# Alimentation.net
KiCad netlist of a schematic drawn in EAGLE
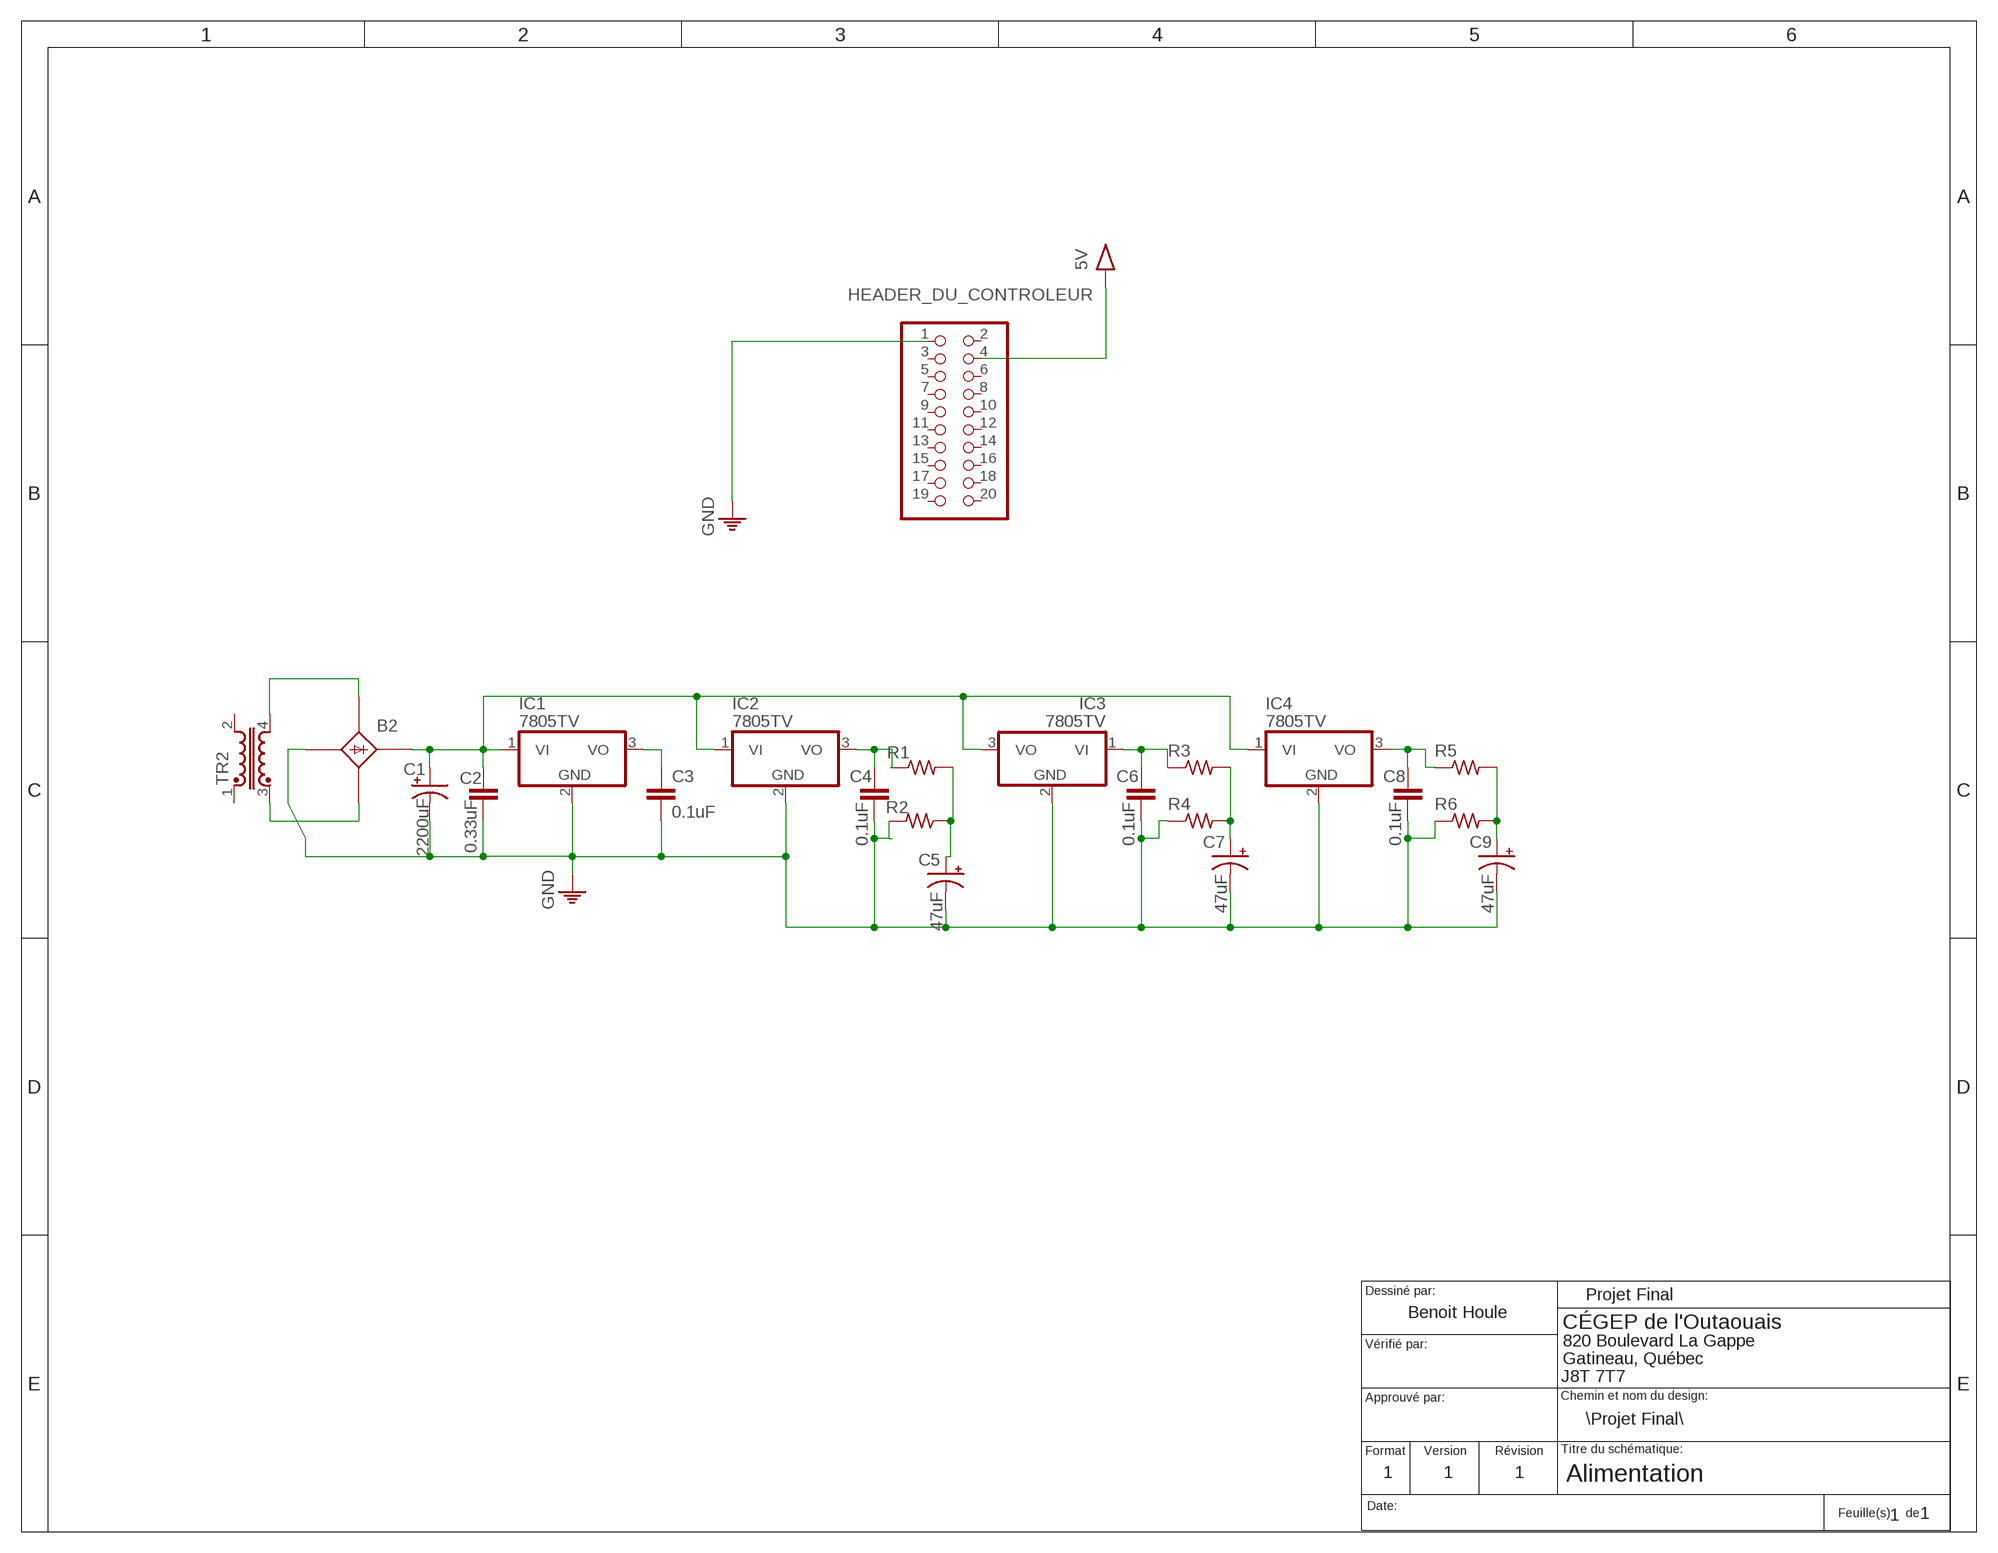
[diagram p0: schematic, sheet 1]

(export (version "E")
  (design (tool "Eeschema 10.0.6"))
  (components
    (comp (ref "B2")
      (value "B25A-")
      (footprint "eagle-import:B25A-")
      (libsource (lib "eagle-import") (part "B25A-"))
    )
    (comp (ref "C1")
      (value "2200uF")
      (footprint "eagle-import:SANYO-OSCON_B'")
      (libsource (lib "eagle-import") (part "CPOL-USSANYO_B'"))
    )
    (comp (ref "C2")
      (value "0.33uF")
      (footprint "eagle-import:C075-032X103")
      (libsource (lib "eagle-import") (part "C-EU075-032X103"))
    )
    (comp (ref "C3")
      (value "0.1uF")
      (footprint "eagle-import:C075-032X103")
      (libsource (lib "eagle-import") (part "C-EU075-032X103"))
    )
    (comp (ref "C4")
      (value "0.1uF")
      (footprint "eagle-import:C075-032X103")
      (libsource (lib "eagle-import") (part "C-EU075-032X103"))
    )
    (comp (ref "C5")
      (value "47uF")
      (footprint "eagle-import:SANYO-OSCON_B'")
      (libsource (lib "eagle-import") (part "CPOL-USSANYO_B'"))
    )
    (comp (ref "C6")
      (value "0.1uF")
      (footprint "eagle-import:C075-032X103")
      (libsource (lib "eagle-import") (part "C-EU075-032X103"))
    )
    (comp (ref "C7")
      (value "47uF")
      (footprint "eagle-import:SANYO-OSCON_B'")
      (libsource (lib "eagle-import") (part "CPOL-USSANYO_B'"))
    )
    (comp (ref "C8")
      (value "0.1uF")
      (footprint "eagle-import:C075-032X103")
      (libsource (lib "eagle-import") (part "C-EU075-032X103"))
    )
    (comp (ref "C9")
      (value "47uF")
      (footprint "eagle-import:SANYO-OSCON_B'")
      (libsource (lib "eagle-import") (part "CPOL-USSANYO_B'"))
    )
    (comp (ref "FRAME1")
      (value "CARTOUCHE_TGÉ")
      (footprint "eagle-import:CARTOUCHE")
      (libsource (lib "eagle-import") (part "CARTOUCHE_TGÉ"))
    )
    (comp (ref "HEADER_DU_CONTROLEUR")
      (value "PINHD-2X10")
      (footprint "eagle-import:2X10")
      (libsource (lib "eagle-import") (part "PINHD-2X10"))
    )
    (comp (ref "IC1")
      (value "7805TV")
      (footprint "eagle-import:TO220V")
      (libsource (lib "eagle-import") (part "78TV05"))
    )
    (comp (ref "IC2")
      (value "7805TV")
      (footprint "eagle-import:TO220V")
      (libsource (lib "eagle-import") (part "78TV05"))
    )
    (comp (ref "IC3")
      (value "7805TV")
      (footprint "eagle-import:TO220V")
      (libsource (lib "eagle-import") (part "78TV05"))
    )
    (comp (ref "IC4")
      (value "7805TV")
      (footprint "eagle-import:TO220V")
      (libsource (lib "eagle-import") (part "78TV05"))
    )
    (comp (ref "R1")
      (value "R-US_0207/15")
      (footprint "eagle-import:0207_15")
      (libsource (lib "eagle-import") (part "R-US_0207/15"))
    )
    (comp (ref "R2")
      (value "R-US_0207/15")
      (footprint "eagle-import:0207_15")
      (libsource (lib "eagle-import") (part "R-US_0207/15"))
    )
    (comp (ref "R3")
      (value "R-US_0207/15")
      (footprint "eagle-import:0207_15")
      (libsource (lib "eagle-import") (part "R-US_0207/15"))
    )
    (comp (ref "R4")
      (value "R-US_0207/15")
      (footprint "eagle-import:0207_15")
      (libsource (lib "eagle-import") (part "R-US_0207/15"))
    )
    (comp (ref "R5")
      (value "R-US_0207/15")
      (footprint "eagle-import:0207_15")
      (libsource (lib "eagle-import") (part "R-US_0207/15"))
    )
    (comp (ref "R6")
      (value "R-US_0207/15")
      (footprint "eagle-import:0207_15")
      (libsource (lib "eagle-import") (part "R-US_0207/15"))
    )
    (comp (ref "TR2")
      (value "U15-TRANSFORMER")
      (footprint "eagle-import:U15")
      (libsource (lib "eagle-import") (part "U15-TRANSFORMER"))
    )
  )
  (nets
    (net (code "1") (name "5V") (class "Default")
      (node (ref "HEADER_DU_CONTROLEUR") (pin "4") (pinfunction "4_4") (pintype "passive"))
    )
    (net (code "2") (name "GND") (class "Default")
      (node (ref "B2") (pin "-1") (pinfunction "-_-1") (pintype "passive"))
      (node (ref "C1") (pin "-") (pinfunction "-_-") (pintype "passive"))
      (node (ref "C2") (pin "2") (pinfunction "2_2") (pintype "passive"))
      (node (ref "C3") (pin "2") (pinfunction "2_2") (pintype "passive"))
      (node (ref "C4") (pin "2") (pinfunction "2_2") (pintype "passive"))
      (node (ref "C5") (pin "-") (pinfunction "-_-") (pintype "passive"))
      (node (ref "C6") (pin "2") (pinfunction "2_2") (pintype "passive"))
      (node (ref "C7") (pin "-") (pinfunction "-_-") (pintype "passive"))
      (node (ref "C8") (pin "2") (pinfunction "2_2") (pintype "passive"))
      (node (ref "C9") (pin "-") (pinfunction "-_-") (pintype "passive"))
      (node (ref "HEADER_DU_CONTROLEUR") (pin "1") (pinfunction "1_1") (pintype "passive"))
      (node (ref "IC1") (pin "2") (pinfunction "GND_2") (pintype "passive"))
      (node (ref "IC2") (pin "2") (pinfunction "GND_2") (pintype "passive"))
      (node (ref "IC3") (pin "2") (pinfunction "GND_2") (pintype "passive"))
      (node (ref "IC4") (pin "2") (pinfunction "GND_2") (pintype "passive"))
      (node (ref "R2") (pin "2") (pinfunction "2_2") (pintype "passive"))
      (node (ref "R4") (pin "1") (pinfunction "1_1") (pintype "passive"))
      (node (ref "R6") (pin "1") (pinfunction "1_1") (pintype "passive"))
    )
    (net (code "3") (name "Net-(B2-AC1-PadAC1-)") (class "Default")
      (node (ref "B2") (pin "AC1-") (pinfunction "AC1_AC1-") (pintype "passive"))
      (node (ref "TR2") (pin "4") (pinfunction "4_4") (pintype "passive"))
    )
    (net (code "4") (name "Net-(B2-AC2-PadAC2-)") (class "Default")
      (node (ref "B2") (pin "AC2-") (pinfunction "AC2_AC2-") (pintype "passive"))
      (node (ref "TR2") (pin "3") (pinfunction "3_3") (pintype "passive"))
    )
    (net (code "5") (name "Net-(C5-Pad+)") (class "Default")
      (node (ref "C5") (pin "+") (pinfunction "+_+") (pintype "passive"))
      (node (ref "R1") (pin "2") (pinfunction "2_2") (pintype "passive"))
      (node (ref "R2") (pin "1") (pinfunction "1_1") (pintype "passive"))
    )
    (net (code "6") (name "Net-(C7-Pad+)") (class "Default")
      (node (ref "C7") (pin "+") (pinfunction "+_+") (pintype "passive"))
      (node (ref "R3") (pin "2") (pinfunction "2_2") (pintype "passive"))
      (node (ref "R4") (pin "2") (pinfunction "2_2") (pintype "passive"))
    )
    (net (code "7") (name "Net-(C9-Pad+)") (class "Default")
      (node (ref "C9") (pin "+") (pinfunction "+_+") (pintype "passive"))
      (node (ref "R5") (pin "2") (pinfunction "2_2") (pintype "passive"))
      (node (ref "R6") (pin "2") (pinfunction "2_2") (pintype "passive"))
    )
    (net (code "8") (name "Net-(IC1-VI)") (class "Default")
      (node (ref "B2") (pin "+1") (pinfunction "+_+1") (pintype "passive"))
      (node (ref "C1") (pin "+") (pinfunction "+_+") (pintype "passive"))
      (node (ref "C2") (pin "1") (pinfunction "1_1") (pintype "passive"))
      (node (ref "IC1") (pin "1") (pinfunction "VI_1") (pintype "input"))
      (node (ref "IC2") (pin "1") (pinfunction "VI_1") (pintype "input"))
      (node (ref "IC3") (pin "3") (pinfunction "VO_3") (pintype "passive"))
      (node (ref "IC4") (pin "1") (pinfunction "VI_1") (pintype "input"))
    )
    (net (code "9") (name "Net-(IC1-VO)") (class "Default")
      (node (ref "C3") (pin "1") (pinfunction "1_1") (pintype "passive"))
      (node (ref "IC1") (pin "3") (pinfunction "VO_3") (pintype "passive"))
    )
    (net (code "10") (name "Net-(IC2-VO)") (class "Default")
      (node (ref "C4") (pin "1") (pinfunction "1_1") (pintype "passive"))
      (node (ref "IC2") (pin "3") (pinfunction "VO_3") (pintype "passive"))
      (node (ref "R1") (pin "1") (pinfunction "1_1") (pintype "passive"))
    )
    (net (code "11") (name "Net-(IC3-VI)") (class "Default")
      (node (ref "C6") (pin "1") (pinfunction "1_1") (pintype "passive"))
      (node (ref "IC3") (pin "1") (pinfunction "VI_1") (pintype "input"))
      (node (ref "R3") (pin "1") (pinfunction "1_1") (pintype "passive"))
    )
    (net (code "12") (name "Net-(IC4-VO)") (class "Default")
      (node (ref "C8") (pin "1") (pinfunction "1_1") (pintype "passive"))
      (node (ref "IC4") (pin "3") (pinfunction "VO_3") (pintype "passive"))
      (node (ref "R5") (pin "1") (pinfunction "1_1") (pintype "passive"))
    )
    (net (code "13") (name "unconnected-(B2-Pad+)") (class "Default")
      (node (ref "B2") (pin "+") (pinfunction "+_+") (pintype "passive"))
    )
    (net (code "14") (name "unconnected-(B2-Pad-)") (class "Default")
      (node (ref "B2") (pin "-") (pinfunction "-_-") (pintype "passive"))
    )
    (net (code "15") (name "unconnected-(B2-PadAC1)") (class "Default")
      (node (ref "B2") (pin "AC1") (pinfunction "AC1_AC1") (pintype "passive"))
    )
    (net (code "16") (name "unconnected-(B2-PadAC2)") (class "Default")
      (node (ref "B2") (pin "AC2") (pinfunction "AC2_AC2") (pintype "passive"))
    )
    (net (code "17") (name "unconnected-(HEADER_DU_CONTROLEUR-Pad2)") (class "Default")
      (node (ref "HEADER_DU_CONTROLEUR") (pin "2") (pinfunction "2_2") (pintype "passive"))
    )
    (net (code "18") (name "unconnected-(HEADER_DU_CONTROLEUR-Pad3)") (class "Default")
      (node (ref "HEADER_DU_CONTROLEUR") (pin "3") (pinfunction "3_3") (pintype "passive"))
    )
    (net (code "19") (name "unconnected-(HEADER_DU_CONTROLEUR-Pad5)") (class "Default")
      (node (ref "HEADER_DU_CONTROLEUR") (pin "5") (pinfunction "5_5") (pintype "passive"))
    )
    (net (code "20") (name "unconnected-(HEADER_DU_CONTROLEUR-Pad6)") (class "Default")
      (node (ref "HEADER_DU_CONTROLEUR") (pin "6") (pinfunction "6_6") (pintype "passive"))
    )
    (net (code "21") (name "unconnected-(HEADER_DU_CONTROLEUR-Pad7)") (class "Default")
      (node (ref "HEADER_DU_CONTROLEUR") (pin "7") (pinfunction "7_7") (pintype "passive"))
    )
    (net (code "22") (name "unconnected-(HEADER_DU_CONTROLEUR-Pad8)") (class "Default")
      (node (ref "HEADER_DU_CONTROLEUR") (pin "8") (pinfunction "8_8") (pintype "passive"))
    )
    (net (code "23") (name "unconnected-(HEADER_DU_CONTROLEUR-Pad9)") (class "Default")
      (node (ref "HEADER_DU_CONTROLEUR") (pin "9") (pinfunction "9_9") (pintype "passive"))
    )
    (net (code "24") (name "unconnected-(HEADER_DU_CONTROLEUR-Pad10)") (class "Default")
      (node (ref "HEADER_DU_CONTROLEUR") (pin "10") (pinfunction "10_10") (pintype "passive"))
    )
    (net (code "25") (name "unconnected-(HEADER_DU_CONTROLEUR-Pad11)") (class "Default")
      (node (ref "HEADER_DU_CONTROLEUR") (pin "11") (pinfunction "11_11") (pintype "passive"))
    )
    (net (code "26") (name "unconnected-(HEADER_DU_CONTROLEUR-Pad12)") (class "Default")
      (node (ref "HEADER_DU_CONTROLEUR") (pin "12") (pinfunction "12_12") (pintype "passive"))
    )
    (net (code "27") (name "unconnected-(HEADER_DU_CONTROLEUR-Pad13)") (class "Default")
      (node (ref "HEADER_DU_CONTROLEUR") (pin "13") (pinfunction "13_13") (pintype "passive"))
    )
    (net (code "28") (name "unconnected-(HEADER_DU_CONTROLEUR-Pad14)") (class "Default")
      (node (ref "HEADER_DU_CONTROLEUR") (pin "14") (pinfunction "14_14") (pintype "passive"))
    )
    (net (code "29") (name "unconnected-(HEADER_DU_CONTROLEUR-Pad15)") (class "Default")
      (node (ref "HEADER_DU_CONTROLEUR") (pin "15") (pinfunction "15_15") (pintype "passive"))
    )
    (net (code "30") (name "unconnected-(HEADER_DU_CONTROLEUR-Pad16)") (class "Default")
      (node (ref "HEADER_DU_CONTROLEUR") (pin "16") (pinfunction "16_16") (pintype "passive"))
    )
    (net (code "31") (name "unconnected-(HEADER_DU_CONTROLEUR-Pad17)") (class "Default")
      (node (ref "HEADER_DU_CONTROLEUR") (pin "17") (pinfunction "17_17") (pintype "passive"))
    )
    (net (code "32") (name "unconnected-(HEADER_DU_CONTROLEUR-Pad18)") (class "Default")
      (node (ref "HEADER_DU_CONTROLEUR") (pin "18") (pinfunction "18_18") (pintype "passive"))
    )
    (net (code "33") (name "unconnected-(HEADER_DU_CONTROLEUR-Pad19)") (class "Default")
      (node (ref "HEADER_DU_CONTROLEUR") (pin "19") (pinfunction "19_19") (pintype "passive"))
    )
    (net (code "34") (name "unconnected-(HEADER_DU_CONTROLEUR-Pad20)") (class "Default")
      (node (ref "HEADER_DU_CONTROLEUR") (pin "20") (pinfunction "20_20") (pintype "passive"))
    )
    (net (code "35") (name "unconnected-(TR2-Pad1)") (class "Default")
      (node (ref "TR2") (pin "1") (pinfunction "1_1") (pintype "passive"))
    )
    (net (code "36") (name "unconnected-(TR2-Pad2)") (class "Default")
      (node (ref "TR2") (pin "2") (pinfunction "2_2") (pintype "passive"))
    )
  )
)
